# SD2SP2_v1p2b.net
KiCad netlist of a schematic drawn in EAGLE
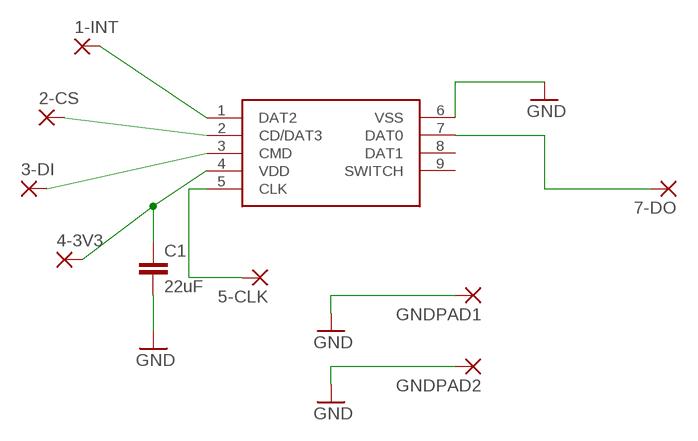
[diagram p0: schematic, sheet 1]

(export (version "E")
  (design (tool "Eeschema 10.0.6"))
  (components
    (comp (ref "1-INT")
      (value "PADSRECTANGLE-1,5X7")
      (footprint "eagle-import:RECTANGLE-1,5X7")
      (libsource (lib "eagle-import") (part "PADSRECTANGLE-1,5X7"))
    )
    (comp (ref "2-CS")
      (value "PADSRECTANGLE-1,5X7")
      (footprint "eagle-import:RECTANGLE-1,5X7")
      (libsource (lib "eagle-import") (part "PADSRECTANGLE-1,5X7"))
    )
    (comp (ref "3-DI")
      (value "PADSRECTANGLE-1,5X7")
      (footprint "eagle-import:RECTANGLE-1,5X7")
      (libsource (lib "eagle-import") (part "PADSRECTANGLE-1,5X7"))
    )
    (comp (ref "4-3V3")
      (value "PADSRECTANGLE-1,5X7")
      (footprint "eagle-import:RECTANGLE-1,5X7")
      (libsource (lib "eagle-import") (part "PADSRECTANGLE-1,5X7"))
    )
    (comp (ref "5-CLK")
      (value "PADSRECTANGLE-1,5X7")
      (footprint "eagle-import:RECTANGLE-1,5X7")
      (libsource (lib "eagle-import") (part "PADSRECTANGLE-1,5X7"))
    )
    (comp (ref "7-DO")
      (value "PADSRECTANGLE-1,5X7")
      (footprint "eagle-import:RECTANGLE-1,5X7")
      (libsource (lib "eagle-import") (part "PADSRECTANGLE-1,5X7"))
    )
    (comp (ref "C1")
      (value "22uF")
      (footprint "eagle-import:C1206")
      (libsource (lib "eagle-import") (part "CAPACITORSC1206"))
    )
    (comp (ref "GNDPAD1")
      (value "PADSRECTANGLE-1,5X7")
      (footprint "eagle-import:RECTANGLE-1,5X7")
      (libsource (lib "eagle-import") (part "PADSRECTANGLE-1,5X7"))
    )
    (comp (ref "GNDPAD2")
      (value "PADSRECTANGLE-1,5X7")
      (footprint "eagle-import:RECTANGLE-1,5X7")
      (libsource (lib "eagle-import") (part "PADSRECTANGLE-1,5X7"))
    )
    (comp (ref "J1")
      (value "SD-CARD-CONNECTOR")
      (footprint "eagle-import:105027-0001")
      (fields
        (field (name "MANUFACTURER_PART_NUMBER") "105027-0001")
        (field (name "MOUSER_PART_NUMBER") "538-105027-0001")
      )
      (libsource (lib "eagle-import") (part "SD-CARD-CONNECTOR"))
    )
  )
  (nets
    (net (code "1") (name "GND") (class "Default")
      (node (ref "C1") (pin "2") (pinfunction "2_2") (pintype "passive"))
      (node (ref "GNDPAD1") (pin "1") (pinfunction "P_1") (pintype "passive"))
      (node (ref "GNDPAD2") (pin "1") (pinfunction "P_1") (pintype "passive"))
      (node (ref "J1") (pin "6") (pinfunction "VSS_6") (pintype "bidirectional"))
    )
    (net (code "2") (name "Net-(1-INT-P)") (class "Default")
      (node (ref "1-INT") (pin "1") (pinfunction "P_1") (pintype "passive"))
      (node (ref "J1") (pin "1") (pinfunction "DAT2_1") (pintype "bidirectional"))
    )
    (net (code "3") (name "Net-(2-CS-P)") (class "Default")
      (node (ref "2-CS") (pin "1") (pinfunction "P_1") (pintype "passive"))
      (node (ref "J1") (pin "2") (pinfunction "CD/DAT3_2") (pintype "bidirectional"))
    )
    (net (code "4") (name "Net-(3-DI-P)") (class "Default")
      (node (ref "3-DI") (pin "1") (pinfunction "P_1") (pintype "passive"))
      (node (ref "J1") (pin "3") (pinfunction "CMD_3") (pintype "bidirectional"))
    )
    (net (code "5") (name "Net-(4-3V3-P)") (class "Default")
      (node (ref "4-3V3") (pin "1") (pinfunction "P_1") (pintype "passive"))
      (node (ref "C1") (pin "1") (pinfunction "1_1") (pintype "passive"))
      (node (ref "J1") (pin "4") (pinfunction "VDD_4") (pintype "bidirectional"))
    )
    (net (code "6") (name "Net-(5-CLK-P)") (class "Default")
      (node (ref "5-CLK") (pin "1") (pinfunction "P_1") (pintype "passive"))
      (node (ref "J1") (pin "5") (pinfunction "CLK_5") (pintype "bidirectional"))
    )
    (net (code "7") (name "Net-(7-DO-P)") (class "Default")
      (node (ref "7-DO") (pin "1") (pinfunction "P_1") (pintype "passive"))
      (node (ref "J1") (pin "7") (pinfunction "DAT0_7") (pintype "bidirectional"))
    )
    (net (code "8") (name "unconnected-(J1-DAT1-Pad8)") (class "Default")
      (node (ref "J1") (pin "8") (pinfunction "DAT1_8") (pintype "bidirectional"))
    )
    (net (code "9") (name "unconnected-(J1-SWITCH-Pad9)") (class "Default")
      (node (ref "J1") (pin "9") (pinfunction "SWITCH_9") (pintype "bidirectional"))
    )
  )
)
